# CARTE_PUISSANCE.net
KiCad netlist of a schematic drawn in EAGLE
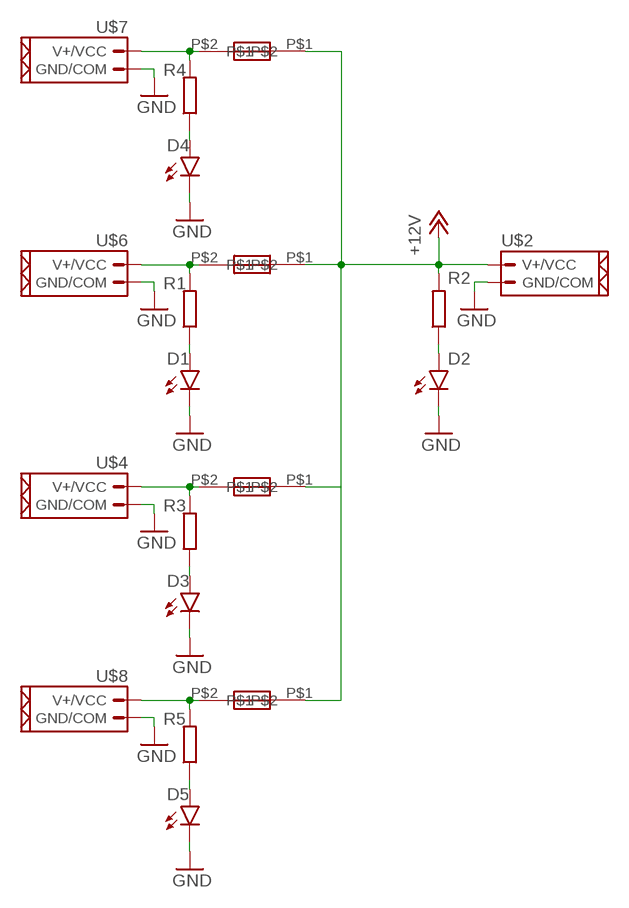
[diagram p0: schematic, sheet 1]

(export (version "E")
  (design (tool "Eeschema 10.0.6"))
  (components
    (comp (ref "D1")
      (value "LED5MM")
      (footprint "eagle-import:LED_5MM")
      (libsource (lib "eagle-import") (part "LED5MM"))
    )
    (comp (ref "D2")
      (value "LED5MM")
      (footprint "eagle-import:LED_5MM")
      (libsource (lib "eagle-import") (part "LED5MM"))
    )
    (comp (ref "D3")
      (value "LED5MM")
      (footprint "eagle-import:LED_5MM")
      (libsource (lib "eagle-import") (part "LED5MM"))
    )
    (comp (ref "D4")
      (value "LED5MM")
      (footprint "eagle-import:LED_5MM")
      (libsource (lib "eagle-import") (part "LED5MM"))
    )
    (comp (ref "D5")
      (value "LED5MM")
      (footprint "eagle-import:LED_5MM")
      (libsource (lib "eagle-import") (part "LED5MM"))
    )
    (comp (ref "R1")
      (value "R-EU_0204/7")
      (footprint "eagle-import:0204_7")
      (libsource (lib "eagle-import") (part "R-EU_0204/7"))
    )
    (comp (ref "R2")
      (value "R-EU_0204/7")
      (footprint "eagle-import:0204_7")
      (libsource (lib "eagle-import") (part "R-EU_0204/7"))
    )
    (comp (ref "R3")
      (value "R-EU_0204/7")
      (footprint "eagle-import:0204_7")
      (libsource (lib "eagle-import") (part "R-EU_0204/7"))
    )
    (comp (ref "R4")
      (value "R-EU_0204/7")
      (footprint "eagle-import:0204_7")
      (libsource (lib "eagle-import") (part "R-EU_0204/7"))
    )
    (comp (ref "R5")
      (value "R-EU_0204/7")
      (footprint "eagle-import:0204_7")
      (libsource (lib "eagle-import") (part "R-EU_0204/7"))
    )
    (comp (ref "U$1")
      (value "AUTOMOTIVE_FUSE")
      (footprint "eagle-import:AUTOMOTIVE_FUSE")
      (libsource (lib "eagle-import") (part "AUTOMOTIVE_FUSE"))
    )
    (comp (ref "U$2")
      (value "CONN_02_PUIXT60")
      (footprint "eagle-import:XT60")
      (libsource (lib "eagle-import") (part "CONN_02_PUIXT60"))
    )
    (comp (ref "U$3")
      (value "AUTOMOTIVE_FUSE")
      (footprint "eagle-import:AUTOMOTIVE_FUSE")
      (libsource (lib "eagle-import") (part "AUTOMOTIVE_FUSE"))
    )
    (comp (ref "U$4")
      (value "CONN_02_PUIXT60")
      (footprint "eagle-import:XT60")
      (libsource (lib "eagle-import") (part "CONN_02_PUIXT60"))
    )
    (comp (ref "U$5")
      (value "AUTOMOTIVE_FUSE")
      (footprint "eagle-import:AUTOMOTIVE_FUSE")
      (libsource (lib "eagle-import") (part "AUTOMOTIVE_FUSE"))
    )
    (comp (ref "U$6")
      (value "CONN_02_PUIXT60")
      (footprint "eagle-import:XT60")
      (libsource (lib "eagle-import") (part "CONN_02_PUIXT60"))
    )
    (comp (ref "U$7")
      (value "CONN_02_PUIXT60")
      (footprint "eagle-import:XT60")
      (libsource (lib "eagle-import") (part "CONN_02_PUIXT60"))
    )
    (comp (ref "U$8")
      (value "CONN_02_PUIXT60")
      (footprint "eagle-import:XT60")
      (libsource (lib "eagle-import") (part "CONN_02_PUIXT60"))
    )
    (comp (ref "U$9")
      (value "AUTOMOTIVE_FUSE")
      (footprint "eagle-import:AUTOMOTIVE_FUSE")
      (libsource (lib "eagle-import") (part "AUTOMOTIVE_FUSE"))
    )
  )
  (nets
    (net (code "1") (name "+12V") (class "Default")
      (node (ref "R2") (pin "2") (pinfunction "2_2") (pintype "passive"))
      (node (ref "U$1") (pin "P$1") (pinfunction "P$1_P$1") (pintype "bidirectional"))
      (node (ref "U$2") (pin "P$1") (pinfunction "V+/VCC_P$1") (pintype "passive"))
      (node (ref "U$3") (pin "P$1") (pinfunction "P$1_P$1") (pintype "bidirectional"))
      (node (ref "U$5") (pin "P$1") (pinfunction "P$1_P$1") (pintype "bidirectional"))
      (node (ref "U$9") (pin "P$1") (pinfunction "P$1_P$1") (pintype "bidirectional"))
    )
    (net (code "2") (name "GND") (class "Default")
      (node (ref "D1") (pin "K") (pinfunction "C_K") (pintype "passive"))
      (node (ref "D2") (pin "K") (pinfunction "C_K") (pintype "passive"))
      (node (ref "D3") (pin "K") (pinfunction "C_K") (pintype "passive"))
      (node (ref "D4") (pin "K") (pinfunction "C_K") (pintype "passive"))
      (node (ref "D5") (pin "K") (pinfunction "C_K") (pintype "passive"))
      (node (ref "U$2") (pin "P$2") (pinfunction "GND/COM_P$2") (pintype "passive"))
      (node (ref "U$4") (pin "P$2") (pinfunction "GND/COM_P$2") (pintype "passive"))
      (node (ref "U$6") (pin "P$2") (pinfunction "GND/COM_P$2") (pintype "passive"))
      (node (ref "U$7") (pin "P$2") (pinfunction "GND/COM_P$2") (pintype "passive"))
      (node (ref "U$8") (pin "P$2") (pinfunction "GND/COM_P$2") (pintype "passive"))
    )
    (net (code "3") (name "Net-(D1-PadA)") (class "Default")
      (node (ref "D1") (pin "A") (pinfunction "A_A") (pintype "passive"))
      (node (ref "R1") (pin "1") (pinfunction "1_1") (pintype "passive"))
    )
    (net (code "4") (name "Net-(D2-PadA)") (class "Default")
      (node (ref "D2") (pin "A") (pinfunction "A_A") (pintype "passive"))
      (node (ref "R2") (pin "1") (pinfunction "1_1") (pintype "passive"))
    )
    (net (code "5") (name "Net-(D3-PadA)") (class "Default")
      (node (ref "D3") (pin "A") (pinfunction "A_A") (pintype "passive"))
      (node (ref "R3") (pin "1") (pinfunction "1_1") (pintype "passive"))
    )
    (net (code "6") (name "Net-(D4-PadA)") (class "Default")
      (node (ref "D4") (pin "A") (pinfunction "A_A") (pintype "passive"))
      (node (ref "R4") (pin "1") (pinfunction "1_1") (pintype "passive"))
    )
    (net (code "7") (name "Net-(D5-PadA)") (class "Default")
      (node (ref "D5") (pin "A") (pinfunction "A_A") (pintype "passive"))
      (node (ref "R5") (pin "1") (pinfunction "1_1") (pintype "passive"))
    )
    (net (code "8") (name "Net-(U$4-V+{slash}VCC)") (class "Default")
      (node (ref "R3") (pin "2") (pinfunction "2_2") (pintype "passive"))
      (node (ref "U$4") (pin "P$1") (pinfunction "V+/VCC_P$1") (pintype "passive"))
      (node (ref "U$5") (pin "P$2") (pinfunction "P$2_P$2") (pintype "bidirectional"))
    )
    (net (code "9") (name "Net-(U$6-V+{slash}VCC)") (class "Default")
      (node (ref "R1") (pin "2") (pinfunction "2_2") (pintype "passive"))
      (node (ref "U$3") (pin "P$2") (pinfunction "P$2_P$2") (pintype "bidirectional"))
      (node (ref "U$6") (pin "P$1") (pinfunction "V+/VCC_P$1") (pintype "passive"))
    )
    (net (code "10") (name "Net-(U$7-V+{slash}VCC)") (class "Default")
      (node (ref "R4") (pin "2") (pinfunction "2_2") (pintype "passive"))
      (node (ref "U$1") (pin "P$2") (pinfunction "P$2_P$2") (pintype "bidirectional"))
      (node (ref "U$7") (pin "P$1") (pinfunction "V+/VCC_P$1") (pintype "passive"))
    )
    (net (code "11") (name "Net-(U$8-V+{slash}VCC)") (class "Default")
      (node (ref "R5") (pin "2") (pinfunction "2_2") (pintype "passive"))
      (node (ref "U$8") (pin "P$1") (pinfunction "V+/VCC_P$1") (pintype "passive"))
      (node (ref "U$9") (pin "P$2") (pinfunction "P$2_P$2") (pintype "bidirectional"))
    )
  )
)
